# 04_Seven_Seg.net
KiCad netlist of a schematic drawn in Altium Designer
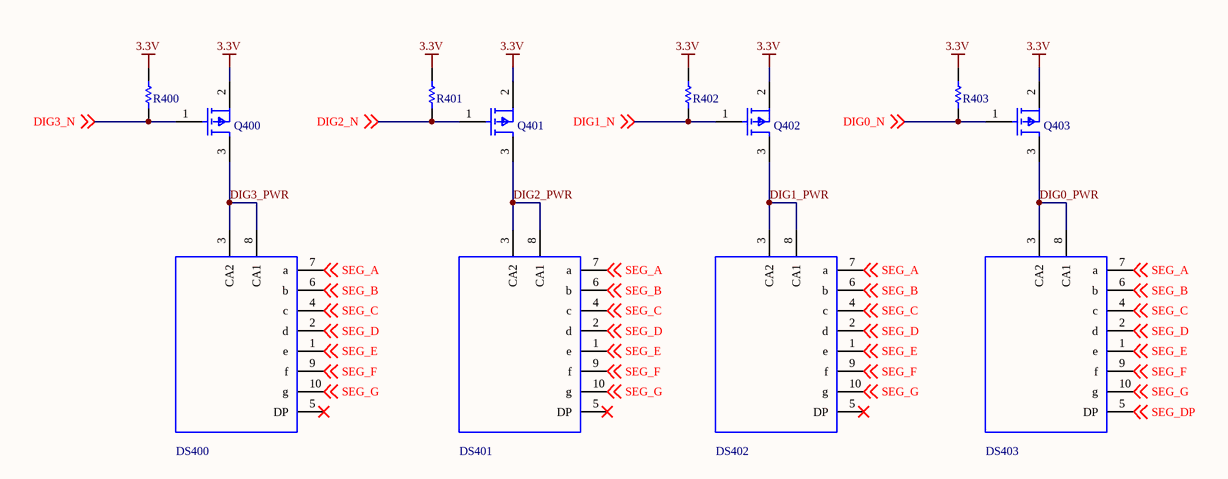
[diagram p0: 04_Seven_Seg.SchDoc]

(export (version "E")
  (design (tool "Eeschema 10.0.6"))
  (components
    (comp (ref "DS400")
      (value "ACSA56-41CGKWA-F01")
      (footprint "ACSA56-41CGKWA-F01")
      (description "DISPLAY 0.56\" SGL 574NM GRN SMD")
      (libsource (lib "LEDs") (part "ACSA56-41CGKWA-F01"))
    )
    (comp (ref "DS401")
      (value "ACSA56-41CGKWA-F01")
      (footprint "ACSA56-41CGKWA-F01")
      (description "DISPLAY 0.56\" SGL 574NM GRN SMD")
      (libsource (lib "LEDs") (part "ACSA56-41CGKWA-F01"))
    )
    (comp (ref "DS402")
      (value "ACSA56-41CGKWA-F01")
      (footprint "ACSA56-41CGKWA-F01")
      (description "DISPLAY 0.56\" SGL 574NM GRN SMD")
      (libsource (lib "LEDs") (part "ACSA56-41CGKWA-F01"))
    )
    (comp (ref "DS403")
      (value "ACSA56-41CGKWA-F01")
      (footprint "ACSA56-41CGKWA-F01")
      (description "DISPLAY 0.56\" SGL 574NM GRN SMD")
      (libsource (lib "LEDs") (part "ACSA56-41CGKWA-F01"))
    )
    (comp (ref "Q400")
      (value "SSM3J328R,LF")
      (footprint "SOT-23_M")
      (description "MOSFET P-CH 20V 6A SOT23F")
      (libsource (lib "Transistors") (part "SSM3J328R,LF"))
    )
    (comp (ref "Q401")
      (value "SSM3J328R,LF")
      (footprint "SOT-23_M")
      (description "MOSFET P-CH 20V 6A SOT23F")
      (libsource (lib "Transistors") (part "SSM3J328R,LF"))
    )
    (comp (ref "Q402")
      (value "SSM3J328R,LF")
      (footprint "SOT-23_M")
      (description "MOSFET P-CH 20V 6A SOT23F")
      (libsource (lib "Transistors") (part "SSM3J328R,LF"))
    )
    (comp (ref "Q403")
      (value "SSM3J328R,LF")
      (footprint "SOT-23_M")
      (description "MOSFET P-CH 20V 6A SOT23F")
      (libsource (lib "Transistors") (part "SSM3J328R,LF"))
    )
    (comp (ref "R400")
      (value "RES_0805_K_010.00")
      (footprint "RES_0805")
      (description "RES SMD 10K OHM 1% 1/8W 0805")
      (fields (field (name "TOLERANCE") "1%"))
      (libsource (lib "Resistors") (part "RES_0805_K_010.00"))
    )
    (comp (ref "R401")
      (value "RES_0805_K_010.00")
      (footprint "RES_0805")
      (description "RES SMD 10K OHM 1% 1/8W 0805")
      (fields (field (name "TOLERANCE") "1%"))
      (libsource (lib "Resistors") (part "RES_0805_K_010.00"))
    )
    (comp (ref "R402")
      (value "RES_0805_K_010.00")
      (footprint "RES_0805")
      (description "RES SMD 10K OHM 1% 1/8W 0805")
      (fields (field (name "TOLERANCE") "1%"))
      (libsource (lib "Resistors") (part "RES_0805_K_010.00"))
    )
    (comp (ref "R403")
      (value "RES_0805_K_010.00")
      (footprint "RES_0805")
      (description "RES SMD 10K OHM 1% 1/8W 0805")
      (fields (field (name "TOLERANCE") "1%"))
      (libsource (lib "Resistors") (part "RES_0805_K_010.00"))
    )
  )
  (nets
    (net (code "1") (name "/DIG0_PWR") (class "Default")
      (node (ref "DS403") (pin "3") (pinfunction "CA2_3") (pintype "passive"))
      (node (ref "DS403") (pin "8") (pinfunction "CA1_8") (pintype "passive"))
      (node (ref "Q403") (pin "3") (pinfunction "Drain_3") (pintype "passive"))
    )
    (net (code "2") (name "/DIG1_PWR") (class "Default")
      (node (ref "DS402") (pin "3") (pinfunction "CA2_3") (pintype "passive"))
      (node (ref "DS402") (pin "8") (pinfunction "CA1_8") (pintype "passive"))
      (node (ref "Q402") (pin "3") (pinfunction "Drain_3") (pintype "passive"))
    )
    (net (code "3") (name "/DIG2_PWR") (class "Default")
      (node (ref "DS401") (pin "3") (pinfunction "CA2_3") (pintype "passive"))
      (node (ref "DS401") (pin "8") (pinfunction "CA1_8") (pintype "passive"))
      (node (ref "Q401") (pin "3") (pinfunction "Drain_3") (pintype "passive"))
    )
    (net (code "4") (name "/DIG3_PWR") (class "Default")
      (node (ref "DS400") (pin "3") (pinfunction "CA2_3") (pintype "passive"))
      (node (ref "DS400") (pin "8") (pinfunction "CA1_8") (pintype "passive"))
      (node (ref "Q400") (pin "3") (pinfunction "Drain_3") (pintype "passive"))
    )
    (net (code "5") (name "3.3V") (class "Default")
      (node (ref "Q400") (pin "2") (pinfunction "Source_2") (pintype "passive"))
      (node (ref "Q401") (pin "2") (pinfunction "Source_2") (pintype "passive"))
      (node (ref "Q402") (pin "2") (pinfunction "Source_2") (pintype "passive"))
      (node (ref "Q403") (pin "2") (pinfunction "Source_2") (pintype "passive"))
      (node (ref "R400") (pin "2") (pinfunction "2_2") (pintype "passive"))
      (node (ref "R401") (pin "2") (pinfunction "2_2") (pintype "passive"))
      (node (ref "R402") (pin "2") (pinfunction "2_2") (pintype "passive"))
      (node (ref "R403") (pin "2") (pinfunction "2_2") (pintype "passive"))
    )
    (net (code "6") (name "DIG0_N") (class "Default")
      (node (ref "Q403") (pin "1") (pinfunction "Gate_1") (pintype "passive"))
      (node (ref "R403") (pin "1") (pinfunction "1_1") (pintype "passive"))
    )
    (net (code "7") (name "DIG1_N") (class "Default")
      (node (ref "Q402") (pin "1") (pinfunction "Gate_1") (pintype "passive"))
      (node (ref "R402") (pin "1") (pinfunction "1_1") (pintype "passive"))
    )
    (net (code "8") (name "DIG2_N") (class "Default")
      (node (ref "Q401") (pin "1") (pinfunction "Gate_1") (pintype "passive"))
      (node (ref "R401") (pin "1") (pinfunction "1_1") (pintype "passive"))
    )
    (net (code "9") (name "DIG3_N") (class "Default")
      (node (ref "Q400") (pin "1") (pinfunction "Gate_1") (pintype "passive"))
      (node (ref "R400") (pin "1") (pinfunction "1_1") (pintype "passive"))
    )
    (net (code "10") (name "SEG_A") (class "Default")
      (node (ref "DS400") (pin "7") (pinfunction "a_7") (pintype "passive"))
      (node (ref "DS401") (pin "7") (pinfunction "a_7") (pintype "passive"))
      (node (ref "DS402") (pin "7") (pinfunction "a_7") (pintype "passive"))
      (node (ref "DS403") (pin "7") (pinfunction "a_7") (pintype "passive"))
    )
    (net (code "11") (name "SEG_B") (class "Default")
      (node (ref "DS400") (pin "6") (pinfunction "b_6") (pintype "passive"))
      (node (ref "DS401") (pin "6") (pinfunction "b_6") (pintype "passive"))
      (node (ref "DS402") (pin "6") (pinfunction "b_6") (pintype "passive"))
      (node (ref "DS403") (pin "6") (pinfunction "b_6") (pintype "passive"))
    )
    (net (code "12") (name "SEG_C") (class "Default")
      (node (ref "DS400") (pin "4") (pinfunction "c_4") (pintype "passive"))
      (node (ref "DS401") (pin "4") (pinfunction "c_4") (pintype "passive"))
      (node (ref "DS402") (pin "4") (pinfunction "c_4") (pintype "passive"))
      (node (ref "DS403") (pin "4") (pinfunction "c_4") (pintype "passive"))
    )
    (net (code "13") (name "SEG_D") (class "Default")
      (node (ref "DS400") (pin "2") (pinfunction "d_2") (pintype "passive"))
      (node (ref "DS401") (pin "2") (pinfunction "d_2") (pintype "passive"))
      (node (ref "DS402") (pin "2") (pinfunction "d_2") (pintype "passive"))
      (node (ref "DS403") (pin "2") (pinfunction "d_2") (pintype "passive"))
    )
    (net (code "14") (name "SEG_DP") (class "Default")
      (node (ref "DS403") (pin "5") (pinfunction "DP_5") (pintype "passive"))
    )
    (net (code "15") (name "SEG_E") (class "Default")
      (node (ref "DS400") (pin "1") (pinfunction "e_1") (pintype "passive"))
      (node (ref "DS401") (pin "1") (pinfunction "e_1") (pintype "passive"))
      (node (ref "DS402") (pin "1") (pinfunction "e_1") (pintype "passive"))
      (node (ref "DS403") (pin "1") (pinfunction "e_1") (pintype "passive"))
    )
    (net (code "16") (name "SEG_F") (class "Default")
      (node (ref "DS400") (pin "9") (pinfunction "f_9") (pintype "passive"))
      (node (ref "DS401") (pin "9") (pinfunction "f_9") (pintype "passive"))
      (node (ref "DS402") (pin "9") (pinfunction "f_9") (pintype "passive"))
      (node (ref "DS403") (pin "9") (pinfunction "f_9") (pintype "passive"))
    )
    (net (code "17") (name "SEG_G") (class "Default")
      (node (ref "DS400") (pin "10") (pinfunction "g_10") (pintype "passive"))
      (node (ref "DS401") (pin "10") (pinfunction "g_10") (pintype "passive"))
      (node (ref "DS402") (pin "10") (pinfunction "g_10") (pintype "passive"))
      (node (ref "DS403") (pin "10") (pinfunction "g_10") (pintype "passive"))
    )
    (net (code "18") (name "unconnected-(DS400-DP-Pad5)") (class "Default")
      (node (ref "DS400") (pin "5") (pinfunction "DP_5") (pintype "passive+no_connect"))
    )
    (net (code "19") (name "unconnected-(DS401-DP-Pad5)") (class "Default")
      (node (ref "DS401") (pin "5") (pinfunction "DP_5") (pintype "passive+no_connect"))
    )
    (net (code "20") (name "unconnected-(DS402-DP-Pad5)") (class "Default")
      (node (ref "DS402") (pin "5") (pinfunction "DP_5") (pintype "passive+no_connect"))
    )
  )
)
